# doorbell20.net
KiCad netlist of a schematic drawn in EAGLE
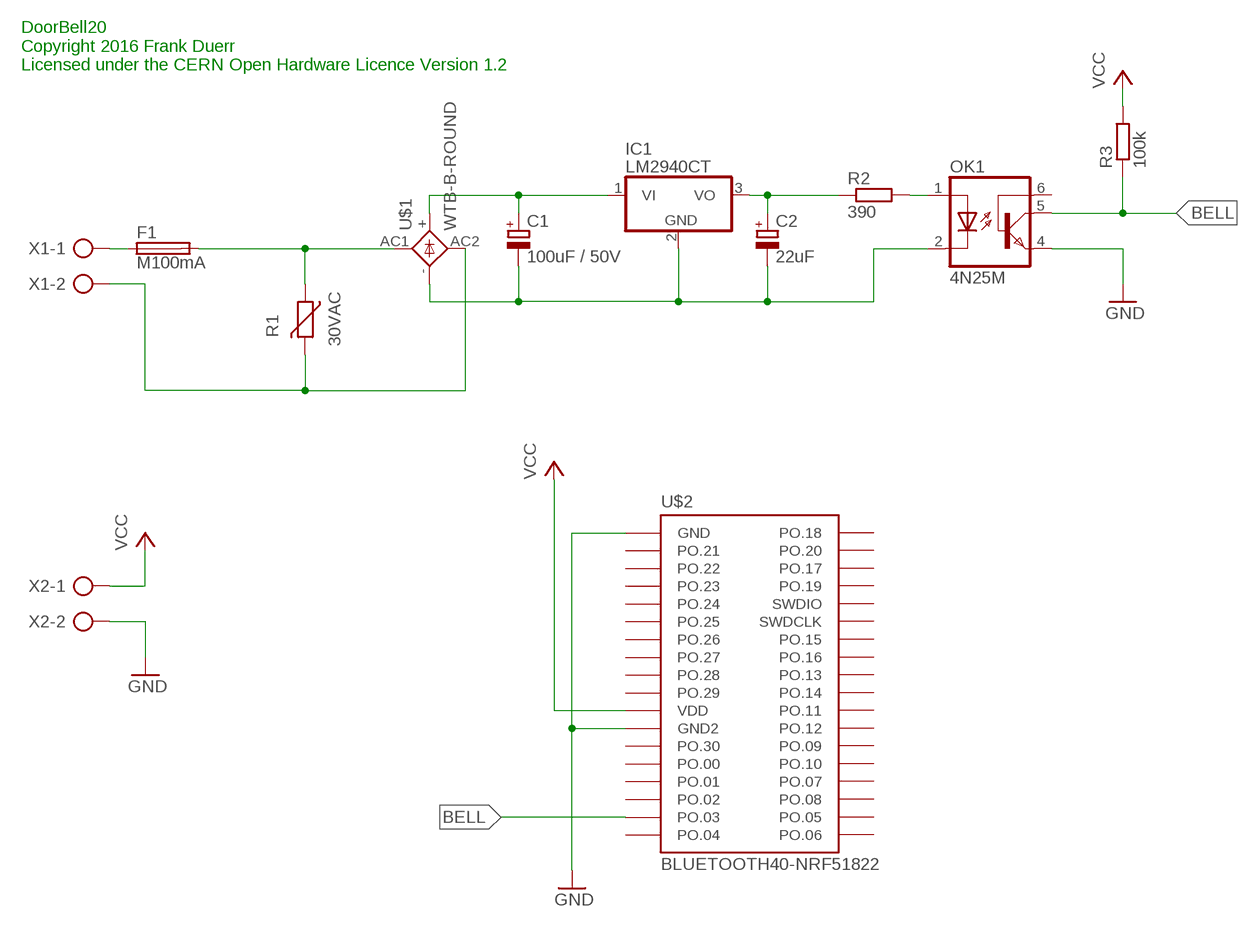
[diagram p0: schematic, sheet 1]

(export (version "E")
  (design (tool "Eeschema 10.0.6"))
  (components
    (comp (ref "C1")
      (value "100uF / 50V")
      (footprint "eagle-import:E5-10,5")
      (libsource (lib "eagle-import") (part "CPOL-EUE5-10.5"))
    )
    (comp (ref "C2")
      (value "22uF")
      (footprint "eagle-import:E2,5-5")
      (libsource (lib "eagle-import") (part "CPOL-EUE2.5-5"))
    )
    (comp (ref "F1")
      (value "M100mA")
      (footprint "eagle-import:SH22,5A")
      (libsource (lib "eagle-import") (part "FUSESH22,5A"))
    )
    (comp (ref "IC1")
      (value "LM2940CT")
      (footprint "eagle-import:TO220V")
      (libsource (lib "eagle-import") (part "78TV05"))
    )
    (comp (ref "OK1")
      (value "4N25M")
      (footprint "eagle-import:DIL06")
      (fields (field (name "MPN") "4N25-M"))
      (libsource (lib "eagle-import") (part "4N?M25"))
    )
    (comp (ref "R1")
      (value "30VAC")
      (footprint "eagle-import:R-7,5")
      (libsource (lib "eagle-import") (part "VARISTOR-7,5"))
    )
    (comp (ref "R2")
      (value "390")
      (footprint "eagle-import:0207_7")
      (libsource (lib "eagle-import") (part "R-EU_0207/7"))
    )
    (comp (ref "R3")
      (value "100k")
      (footprint "eagle-import:0207_7")
      (libsource (lib "eagle-import") (part "R-EU_0207/7"))
    )
    (comp (ref "U$1")
      (value "WTB-B-ROUND")
      (footprint "eagle-import:WTE-B-ROUND")
      (libsource (lib "eagle-import") (part "WTB-B-ROUND"))
    )
    (comp (ref "U$2")
      (value "BLUETOOTH40-NRF51822")
      (footprint "eagle-import:BLUETOOTH40-NR51822")
      (libsource (lib "eagle-import") (part "BLUETOOTH40-NRF51822"))
    )
    (comp (ref "X1")
      (value "AK500/2")
      (footprint "eagle-import:AK500_2")
      (libsource (lib "eagle-import") (part "AK500/2"))
    )
    (comp (ref "X2")
      (value "AK500/2")
      (footprint "eagle-import:AK500_2")
      (libsource (lib "eagle-import") (part "AK500/2"))
    )
  )
  (nets
    (net (code "1") (name "BELL") (class "Default")
      (node (ref "OK1") (pin "5") (pinfunction "COL_5") (pintype "passive"))
      (node (ref "R3") (pin "1") (pinfunction "1_1") (pintype "passive"))
      (node (ref "U$2") (pin "PO.03") (pinfunction "PO.03_PO.03") (pintype "bidirectional"))
    )
    (net (code "2") (name "GND") (class "Default")
      (node (ref "OK1") (pin "4") (pinfunction "EMI_4") (pintype "passive"))
      (node (ref "U$2") (pin "GND") (pinfunction "GND_GND") (pintype "power_in"))
      (node (ref "U$2") (pin "GND2") (pinfunction "GND2_GND2") (pintype "power_in"))
      (node (ref "X2") (pin "2") (pinfunction "KL_2") (pintype "passive"))
    )
    (net (code "3") (name "Net-(F1-Pad2)") (class "Default")
      (node (ref "F1") (pin "2") (pinfunction "2_2") (pintype "passive"))
      (node (ref "R1") (pin "1") (pinfunction "1_1") (pintype "passive"))
      (node (ref "U$1") (pin "AC1") (pinfunction "AC1_AC1") (pintype "passive"))
    )
    (net (code "4") (name "Net-(IC1-GND)") (class "Default")
      (node (ref "C1") (pin "-") (pinfunction "-_-") (pintype "passive"))
      (node (ref "C2") (pin "-") (pinfunction "-_-") (pintype "passive"))
      (node (ref "IC1") (pin "2") (pinfunction "GND_2") (pintype "passive"))
      (node (ref "OK1") (pin "2") (pinfunction "C_2") (pintype "passive"))
      (node (ref "U$1") (pin "-") (pinfunction "-_-") (pintype "passive"))
    )
    (net (code "5") (name "Net-(IC1-VI)") (class "Default")
      (node (ref "C1") (pin "+") (pinfunction "+_+") (pintype "passive"))
      (node (ref "IC1") (pin "1") (pinfunction "VI_1") (pintype "input"))
      (node (ref "U$1") (pin "+") (pinfunction "+_+") (pintype "passive"))
    )
    (net (code "6") (name "Net-(IC1-VO)") (class "Default")
      (node (ref "C2") (pin "+") (pinfunction "+_+") (pintype "passive"))
      (node (ref "IC1") (pin "3") (pinfunction "VO_3") (pintype "passive"))
      (node (ref "R2") (pin "1") (pinfunction "1_1") (pintype "passive"))
    )
    (net (code "7") (name "Net-(OK1-A)") (class "Default")
      (node (ref "OK1") (pin "1") (pinfunction "A_1") (pintype "passive"))
      (node (ref "R2") (pin "2") (pinfunction "2_2") (pintype "passive"))
    )
    (net (code "8") (name "Net-(X1A-KL)") (class "Default")
      (node (ref "F1") (pin "1") (pinfunction "1_1") (pintype "passive"))
      (node (ref "X1") (pin "1") (pinfunction "KL_1") (pintype "passive"))
    )
    (net (code "9") (name "Net-(X1B-KL)") (class "Default")
      (node (ref "R1") (pin "2") (pinfunction "2_2") (pintype "passive"))
      (node (ref "U$1") (pin "AC2") (pinfunction "AC2_AC2") (pintype "passive"))
      (node (ref "X1") (pin "2") (pinfunction "KL_2") (pintype "passive"))
    )
    (net (code "10") (name "VCC") (class "Default")
      (node (ref "R3") (pin "2") (pinfunction "2_2") (pintype "passive"))
      (node (ref "U$2") (pin "VDD") (pinfunction "VDD_VDD") (pintype "power_in"))
      (node (ref "X2") (pin "1") (pinfunction "KL_1") (pintype "passive"))
    )
    (net (code "11") (name "unconnected-(OK1-BAS-Pad6)") (class "Default")
      (node (ref "OK1") (pin "6") (pinfunction "BAS_6") (pintype "passive"))
    )
    (net (code "12") (name "unconnected-(U$2-PadPO.00)") (class "Default")
      (node (ref "U$2") (pin "PO.00") (pinfunction "PO.00_PO.00") (pintype "bidirectional"))
    )
    (net (code "13") (name "unconnected-(U$2-PadPO.01)") (class "Default")
      (node (ref "U$2") (pin "PO.01") (pinfunction "PO.01_PO.01") (pintype "bidirectional"))
    )
    (net (code "14") (name "unconnected-(U$2-PadPO.02)") (class "Default")
      (node (ref "U$2") (pin "PO.02") (pinfunction "PO.02_PO.02") (pintype "bidirectional"))
    )
    (net (code "15") (name "unconnected-(U$2-PadPO.04)") (class "Default")
      (node (ref "U$2") (pin "PO.04") (pinfunction "PO.04_PO.04") (pintype "bidirectional"))
    )
    (net (code "16") (name "unconnected-(U$2-PadPO.05)") (class "Default")
      (node (ref "U$2") (pin "PO.05") (pinfunction "PO.05_PO.05") (pintype "bidirectional"))
    )
    (net (code "17") (name "unconnected-(U$2-PadPO.06)") (class "Default")
      (node (ref "U$2") (pin "PO.06") (pinfunction "PO.06_PO.06") (pintype "bidirectional"))
    )
    (net (code "18") (name "unconnected-(U$2-PadPO.07)") (class "Default")
      (node (ref "U$2") (pin "PO.07") (pinfunction "PO.07_PO.07") (pintype "bidirectional"))
    )
    (net (code "19") (name "unconnected-(U$2-PadPO.08)") (class "Default")
      (node (ref "U$2") (pin "PO.08") (pinfunction "PO.08_PO.08") (pintype "bidirectional"))
    )
    (net (code "20") (name "unconnected-(U$2-PadPO.09)") (class "Default")
      (node (ref "U$2") (pin "PO.09") (pinfunction "PO.09_PO.09") (pintype "bidirectional"))
    )
    (net (code "21") (name "unconnected-(U$2-PadPO.10)") (class "Default")
      (node (ref "U$2") (pin "PO.10") (pinfunction "PO.10_PO.10") (pintype "bidirectional"))
    )
    (net (code "22") (name "unconnected-(U$2-PadPO.11)") (class "Default")
      (node (ref "U$2") (pin "PO.11") (pinfunction "PO.11_PO.11") (pintype "bidirectional"))
    )
    (net (code "23") (name "unconnected-(U$2-PadPO.12)") (class "Default")
      (node (ref "U$2") (pin "PO.12") (pinfunction "PO.12_PO.12") (pintype "bidirectional"))
    )
    (net (code "24") (name "unconnected-(U$2-PadPO.13)") (class "Default")
      (node (ref "U$2") (pin "PO.13") (pinfunction "PO.13_PO.13") (pintype "bidirectional"))
    )
    (net (code "25") (name "unconnected-(U$2-PadPO.14)") (class "Default")
      (node (ref "U$2") (pin "PO.14") (pinfunction "PO.14_PO.14") (pintype "bidirectional"))
    )
    (net (code "26") (name "unconnected-(U$2-PadPO.15)") (class "Default")
      (node (ref "U$2") (pin "PO.15") (pinfunction "PO.15_PO.15") (pintype "bidirectional"))
    )
    (net (code "27") (name "unconnected-(U$2-PadPO.16)") (class "Default")
      (node (ref "U$2") (pin "PO.16") (pinfunction "PO.16_PO.16") (pintype "bidirectional"))
    )
    (net (code "28") (name "unconnected-(U$2-PadPO.17)") (class "Default")
      (node (ref "U$2") (pin "PO.17") (pinfunction "PO.17_PO.17") (pintype "bidirectional"))
    )
    (net (code "29") (name "unconnected-(U$2-PadPO.18)") (class "Default")
      (node (ref "U$2") (pin "PO.18") (pinfunction "PO.18_PO.18") (pintype "bidirectional"))
    )
    (net (code "30") (name "unconnected-(U$2-PadPO.19)") (class "Default")
      (node (ref "U$2") (pin "PO.19") (pinfunction "PO.19_PO.19") (pintype "bidirectional"))
    )
    (net (code "31") (name "unconnected-(U$2-PadPO.20)") (class "Default")
      (node (ref "U$2") (pin "PO.20") (pinfunction "PO.20_PO.20") (pintype "bidirectional"))
    )
    (net (code "32") (name "unconnected-(U$2-PadPO.21)") (class "Default")
      (node (ref "U$2") (pin "PO.21") (pinfunction "PO.21_PO.21") (pintype "bidirectional"))
    )
    (net (code "33") (name "unconnected-(U$2-PadPO.22)") (class "Default")
      (node (ref "U$2") (pin "PO.22") (pinfunction "PO.22_PO.22") (pintype "bidirectional"))
    )
    (net (code "34") (name "unconnected-(U$2-PadPO.23)") (class "Default")
      (node (ref "U$2") (pin "PO.23") (pinfunction "PO.23_PO.23") (pintype "bidirectional"))
    )
    (net (code "35") (name "unconnected-(U$2-PadPO.24)") (class "Default")
      (node (ref "U$2") (pin "PO.24") (pinfunction "PO.24_PO.24") (pintype "bidirectional"))
    )
    (net (code "36") (name "unconnected-(U$2-PadPO.25)") (class "Default")
      (node (ref "U$2") (pin "PO.25") (pinfunction "PO.25_PO.25") (pintype "bidirectional"))
    )
    (net (code "37") (name "unconnected-(U$2-PadPO.26)") (class "Default")
      (node (ref "U$2") (pin "PO.26") (pinfunction "PO.26_PO.26") (pintype "bidirectional"))
    )
    (net (code "38") (name "unconnected-(U$2-PadPO.27)") (class "Default")
      (node (ref "U$2") (pin "PO.27") (pinfunction "PO.27_PO.27") (pintype "bidirectional"))
    )
    (net (code "39") (name "unconnected-(U$2-PadPO.28)") (class "Default")
      (node (ref "U$2") (pin "PO.28") (pinfunction "PO.28_PO.28") (pintype "bidirectional"))
    )
    (net (code "40") (name "unconnected-(U$2-PadPO.29)") (class "Default")
      (node (ref "U$2") (pin "PO.29") (pinfunction "PO.29_PO.29") (pintype "bidirectional"))
    )
    (net (code "41") (name "unconnected-(U$2-PadPO.30)") (class "Default")
      (node (ref "U$2") (pin "PO.30") (pinfunction "PO.30_PO.30") (pintype "bidirectional"))
    )
    (net (code "42") (name "unconnected-(U$2-PadSWDCLK)") (class "Default")
      (node (ref "U$2") (pin "SWDCLK") (pinfunction "SWDCLK_SWDCLK") (pintype "bidirectional"))
    )
    (net (code "43") (name "unconnected-(U$2-PadSWDIO)") (class "Default")
      (node (ref "U$2") (pin "SWDIO") (pinfunction "SWDIO_SWDIO") (pintype "bidirectional"))
    )
  )
)
